# fat41p.net
KiCad netlist of a schematic drawn in Altium Designer
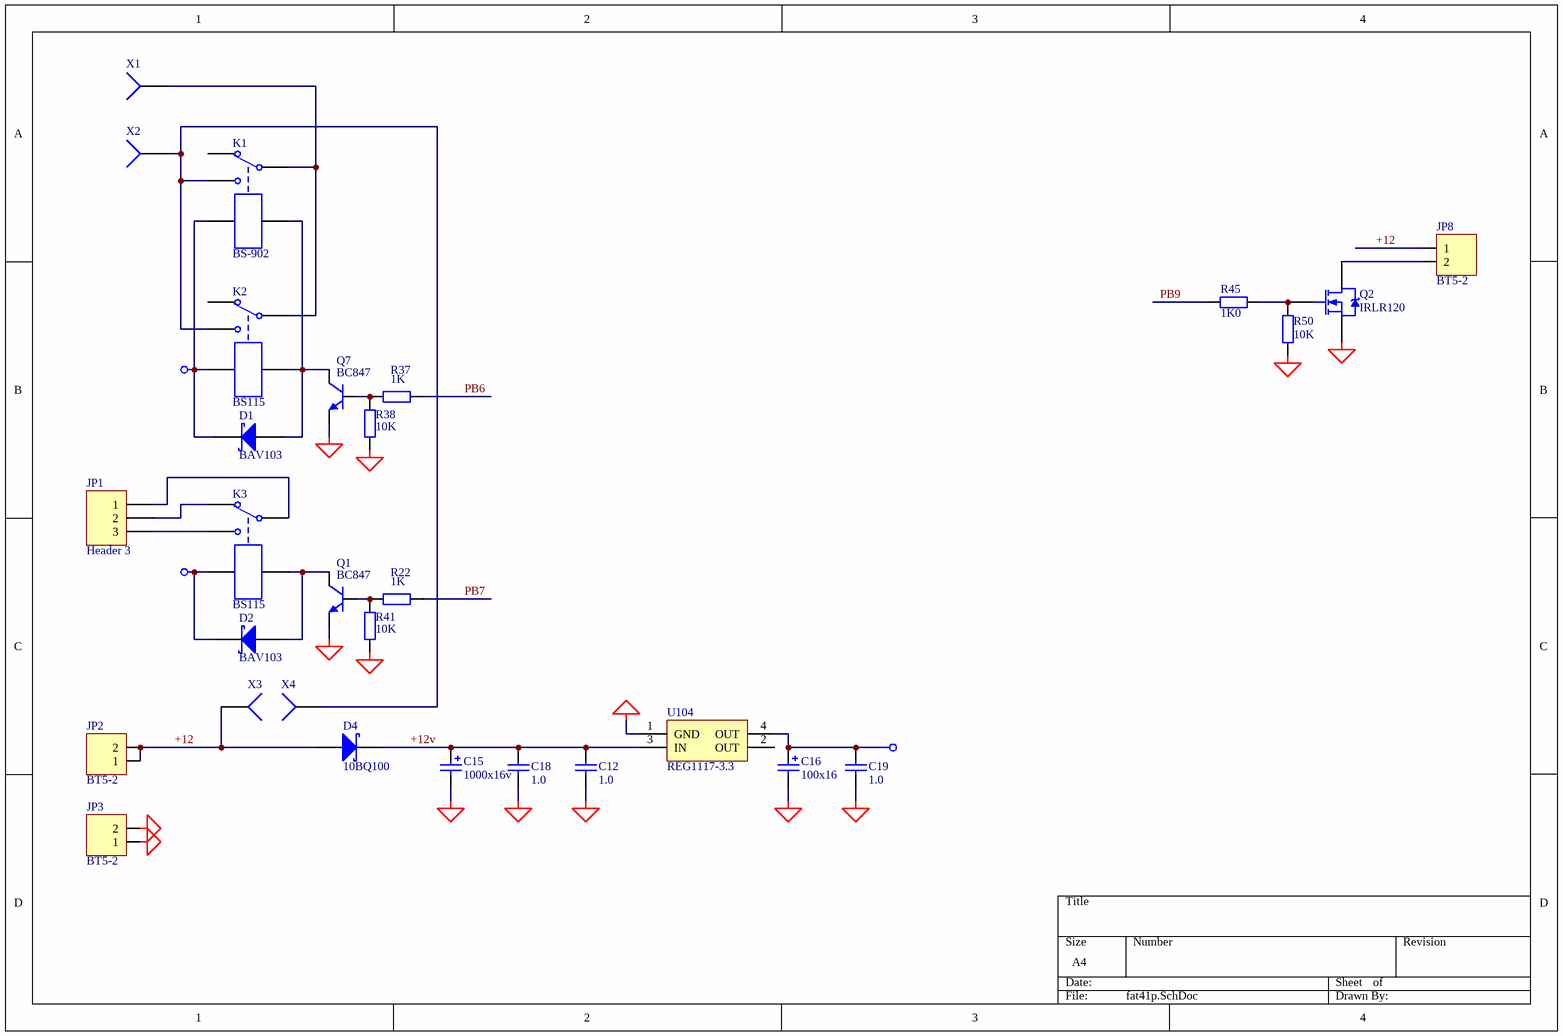
[diagram p0: fat41p.SchDoc]

(export (version "E")
  (design (tool "Eeschema 10.0.6"))
  (components
    (comp (ref "C12")
      (value "Cap")
      (footprint "_1206")
      (description "Capacitor")
      (fields
        (field (name "MANUFACTURER") "Generic Components")
        (field (name "ALTIUM_VALUE") "1.0")
        (field (name "PUBLISHER") "Altium Limited")
      )
      (libsource (lib "BUF") (part "Cap"))
    )
    (comp (ref "C15")
      (value "1000x16v")
      (footprint "el5")
      (description "Polarized Capacitor (Radial)")
      (fields (field (name "MANUFACTURER") "Generic Components") (field (name "PUBLISHER") "Altium Limited"))
      (libsource (lib "BUF") (part "Cap Pol1"))
    )
    (comp (ref "C16")
      (value "100x16")
      (footprint "el3")
      (description "Polarized Capacitor (Radial)")
      (fields (field (name "MANUFACTURER") "Generic Components") (field (name "PUBLISHER") "Altium Limited"))
      (libsource (lib "BUF") (part "Cap Pol"))
    )
    (comp (ref "C18")
      (value "Cap")
      (footprint "_1206")
      (description "Capacitor")
      (fields
        (field (name "MANUFACTURER") "Generic Components")
        (field (name "ALTIUM_VALUE") "1.0")
        (field (name "PUBLISHER") "Altium Limited")
      )
      (libsource (lib "BUF") (part "Cap"))
    )
    (comp (ref "C19")
      (value "Cap")
      (footprint "_1206")
      (description "Capacitor")
      (fields
        (field (name "MANUFACTURER") "Generic Components")
        (field (name "ALTIUM_VALUE") "1.0")
        (field (name "PUBLISHER") "Altium Limited")
      )
      (libsource (lib "BUF") (part "Cap"))
    )
    (comp (ref "D1")
      (value "BAV103")
      (footprint "_1206d")
      (description "Schottky Rectifier")
      (fields
        (field (name "MANUFACTURER") "International Rectifier")
        (field (name "PUBLISHER") "Altium Limited")
      )
      (libsource (lib "IR Discrete Diode") (part "10BQ015"))
    )
    (comp (ref "D2")
      (value "BAV103")
      (footprint "_1206d")
      (description "Schottky Rectifier")
      (fields
        (field (name "MANUFACTURER") "International Rectifier")
        (field (name "PUBLISHER") "Altium Limited")
      )
      (libsource (lib "IR Discrete Diode") (part "10BQ015"))
    )
    (comp (ref "D4")
      (value "10BQ100")
      (footprint "DSO-C2/X2.3")
      (description "Schottky Rectifier")
      (fields
        (field (name "MANUFACTURER") "International Rectifier")
        (field (name "PUBLISHER") "Altium Limited")
      )
      (libsource (lib "IR Discrete Diode") (part "10BQ015"))
    )
    (comp (ref "JP1")
      (value "Header 3")
      (footprint "BT5-3")
      (description "Header, 3-Pin")
      (fields (field (name "MANUFACTURER") "Generic Components") (field (name "PUBLISHER") "Altium Limited"))
      (libsource (lib "Miscellaneous Connectors") (part "Header 3"))
    )
    (comp (ref "JP2")
      (value "BT5-2")
      (footprint "BT5-2-1")
      (description "Header, 3-Pin")
      (fields (field (name "MANUFACTURER") "Generic Components") (field (name "PUBLISHER") "Altium Limited"))
      (libsource (lib "") (part "BT5-2_1"))
    )
    (comp (ref "JP3")
      (value "BT5-2")
      (footprint "BT5-2-1")
      (description "Header, 3-Pin")
      (fields (field (name "MANUFACTURER") "Generic Components") (field (name "PUBLISHER") "Altium Limited"))
      (libsource (lib "") (part "BT5-2_1"))
    )
    (comp (ref "JP8")
      (value "BT5-2")
      (footprint "BT5-2-1")
      (description "Header, 3-Pin")
      (fields (field (name "MANUFACTURER") "Generic Components") (field (name "PUBLISHER") "Altium Limited"))
      (libsource (lib "PAL") (part "BT5-2"))
    )
    (comp (ref "K1")
      (value "BS-902")
      (footprint "BS-902")
      (description "Single-Pole Dual-Throw Relay")
      (fields (field (name "MANUFACTURER") "Generic Components") (field (name "PUBLISHER") "Altium Limited"))
      (libsource (lib "PAL") (part "BS115"))
    )
    (comp (ref "K2")
      (value "BS115")
      (footprint "BS115")
      (description "Single-Pole Dual-Throw Relay")
      (fields (field (name "MANUFACTURER") "Generic Components") (field (name "PUBLISHER") "Altium Limited"))
      (libsource (lib "PAL") (part "BS115"))
    )
    (comp (ref "K3")
      (value "BS115")
      (footprint "BS115")
      (description "Single-Pole Dual-Throw Relay")
      (fields (field (name "MANUFACTURER") "Generic Components") (field (name "PUBLISHER") "Altium Limited"))
      (libsource (lib "PAL") (part "BS115"))
    )
    (comp (ref "Q1")
      (value "BC847")
      (footprint "SO-G3")
      (description "General Purpose Transistor NPN Silicon")
      (fields (field (name "MANUFACTURER") "Motorola") (field (name "PUBLISHER") "Altium Limited"))
      (libsource (lib "PAL") (part "BC847ALT1"))
    )
    (comp (ref "Q2")
      (value "IRLR120")
      (footprint "SIP-G3/E8")
      (description "HEXFET N-Channel Power MOSFET")
      (fields
        (field (name "MANUFACTURER") "International Rectifier")
        (field (name "PUBLISHER") "Altium Limited")
      )
      (libsource (lib "IR Discrete MOSFET") (part "IRFR120"))
    )
    (comp (ref "Q7")
      (value "BC847")
      (footprint "SO-G3")
      (description "General Purpose Transistor NPN Silicon")
      (fields (field (name "MANUFACTURER") "Motorola") (field (name "PUBLISHER") "Altium Limited"))
      (libsource (lib "PAL") (part "BC847ALT1"))
    )
    (comp (ref "R22")
      (value "Res2")
      (footprint "_1206")
      (description "Resistor")
      (fields
        (field (name "MANUFACTURER") "Generic Components")
        (field (name "ALTIUM_VALUE") "1K")
        (field (name "PUBLISHER") "Altium Limited")
      )
      (libsource (lib "Miscellaneous Devices") (part "Res2"))
    )
    (comp (ref "R37")
      (value "Res2")
      (footprint "_1206")
      (description "Resistor")
      (fields
        (field (name "MANUFACTURER") "Generic Components")
        (field (name "ALTIUM_VALUE") "1K")
        (field (name "PUBLISHER") "Altium Limited")
      )
      (libsource (lib "Miscellaneous Devices") (part "Res2"))
    )
    (comp (ref "R38")
      (value "Res2")
      (footprint "_1206")
      (description "Resistor")
      (fields
        (field (name "MANUFACTURER") "Generic Components")
        (field (name "ALTIUM_VALUE") "10K")
        (field (name "PUBLISHER") "Altium Limited")
      )
      (libsource (lib "") (part "Res2_1"))
    )
    (comp (ref "R41")
      (value "Res2")
      (footprint "_1206")
      (description "Resistor")
      (fields
        (field (name "MANUFACTURER") "Generic Components")
        (field (name "ALTIUM_VALUE") "10K")
        (field (name "PUBLISHER") "Altium Limited")
      )
      (libsource (lib "") (part "Res2_1"))
    )
    (comp (ref "R45")
      (value "1K0")
      (footprint "_1206")
      (description "Resistor")
      (fields (field (name "MANUFACTURER") "Generic Components") (field (name "PUBLISHER") "Altium Limited"))
      (libsource (lib "Miscellaneous Devices") (part "Res2"))
    )
    (comp (ref "R50")
      (value "10K")
      (footprint "_1206")
      (description "Resistor")
      (fields (field (name "MANUFACTURER") "Generic Components") (field (name "PUBLISHER") "Altium Limited"))
      (libsource (lib "") (part "Res2_1"))
    )
    (comp (ref "U104")
      (value "REG1117-3.3")
      (footprint "SIP-G3/C7.4")
      (description "800mA and 1A Low Dropout Positive Regulator 2.85V, 3.3V, 5V, and Adjustable")
      (fields (field (name "MANUFACTURER") "Burr-Brown") (field (name "PUBLISHER") "Altium Limited"))
      (libsource (lib "BB Power Mgt Voltage Regulator") (part "REG1117-3.3"))
    )
    (comp (ref "X1")
      (value "~")
      (footprint "PAL:PIN3")
      (description "Socket")
      (fields (field (name "MANUFACTURER") "Generic Components") (field (name "PUBLISHER") "Altium Limited"))
      (libsource (lib "Miscellaneous Connectors") (part "Socket"))
    )
    (comp (ref "X2")
      (value "~")
      (footprint "PAL:PIN3")
      (description "Socket")
      (fields (field (name "MANUFACTURER") "Generic Components") (field (name "PUBLISHER") "Altium Limited"))
      (libsource (lib "Miscellaneous Connectors") (part "Socket"))
    )
    (comp (ref "X3")
      (value "~")
      (footprint "PIN1")
      (description "Socket")
      (fields (field (name "MANUFACTURER") "Generic Components") (field (name "PUBLISHER") "Altium Limited"))
      (libsource (lib "Miscellaneous Connectors") (part "Socket"))
    )
    (comp (ref "X4")
      (value "~")
      (footprint "PIN1")
      (description "Socket")
      (fields (field (name "MANUFACTURER") "Generic Components") (field (name "PUBLISHER") "Altium Limited"))
      (libsource (lib "Miscellaneous Connectors") (part "Socket"))
    )
  )
  (nets
    (net (code "1") (name "+3v3") (class "Default")
      (node (ref "C16") (pin "1") (pinfunction "1_1") (pintype "passive"))
      (node (ref "C19") (pin "2") (pinfunction "2_2") (pintype "passive"))
      (node (ref "U104") (pin "4") (pinfunction "OUT_4") (pintype "power_in"))
    )
    (net (code "2") (name "+12v") (class "Default")
      (node (ref "C12") (pin "2") (pinfunction "2_2") (pintype "passive"))
      (node (ref "C15") (pin "1") (pinfunction "1_1") (pintype "passive"))
      (node (ref "C18") (pin "2") (pinfunction "2_2") (pintype "passive"))
      (node (ref "D1") (pin "2") (pinfunction "K_2") (pintype "passive"))
      (node (ref "D2") (pin "2") (pinfunction "K_2") (pintype "passive"))
      (node (ref "D4") (pin "2") (pinfunction "K_2") (pintype "passive"))
      (node (ref "K1") (pin "5") (pinfunction "5_5") (pintype "passive"))
      (node (ref "K2") (pin "5") (pinfunction "5_5") (pintype "passive"))
      (node (ref "K3") (pin "5") (pinfunction "5_5") (pintype "passive"))
      (node (ref "U104") (pin "3") (pinfunction "IN_3") (pintype "power_in"))
    )
    (net (code "3") (name "/+12") (class "Default")
      (node (ref "D4") (pin "1") (pinfunction "A_1") (pintype "passive"))
      (node (ref "JP2") (pin "1") (pinfunction "1_1") (pintype "passive"))
      (node (ref "JP2") (pin "2") (pinfunction "2_2") (pintype "passive"))
      (node (ref "JP8") (pin "1") (pinfunction "1_1") (pintype "passive"))
      (node (ref "X3") (pin "1") (pinfunction "1_1") (pintype "passive"))
    )
    (net (code "4") (name "/PB6") (class "Default")
      (node (ref "R37") (pin "2") (pinfunction "2_2") (pintype "passive"))
    )
    (net (code "5") (name "/PB7") (class "Default")
      (node (ref "R22") (pin "2") (pinfunction "2_2") (pintype "passive"))
    )
    (net (code "6") (name "/PB9") (class "Default")
      (node (ref "R45") (pin "1") (pinfunction "1_1") (pintype "passive"))
    )
    (net (code "7") (name "GND") (class "Default")
      (node (ref "C12") (pin "1") (pinfunction "1_1") (pintype "passive"))
      (node (ref "C15") (pin "2") (pinfunction "2_2") (pintype "passive"))
      (node (ref "C16") (pin "2") (pinfunction "2_2") (pintype "passive"))
      (node (ref "C18") (pin "1") (pinfunction "1_1") (pintype "passive"))
      (node (ref "C19") (pin "1") (pinfunction "1_1") (pintype "passive"))
      (node (ref "JP3") (pin "1") (pinfunction "1_1") (pintype "passive"))
      (node (ref "JP3") (pin "2") (pinfunction "2_2") (pintype "passive"))
      (node (ref "Q1") (pin "2") (pinfunction "E_2") (pintype "passive"))
      (node (ref "Q2") (pin "3") (pinfunction "S_3") (pintype "passive"))
      (node (ref "Q7") (pin "2") (pinfunction "E_2") (pintype "passive"))
      (node (ref "R38") (pin "2") (pinfunction "2_2") (pintype "passive"))
      (node (ref "R41") (pin "2") (pinfunction "2_2") (pintype "passive"))
      (node (ref "R50") (pin "2") (pinfunction "2_2") (pintype "passive"))
      (node (ref "U104") (pin "1") (pinfunction "GND_1") (pintype "power_in"))
    )
    (net (code "8") (name "Net-(D1-A)") (class "Default")
      (node (ref "D1") (pin "1") (pinfunction "A_1") (pintype "passive"))
      (node (ref "K1") (pin "4") (pinfunction "4_4") (pintype "passive"))
      (node (ref "K2") (pin "4") (pinfunction "4_4") (pintype "passive"))
      (node (ref "Q7") (pin "3") (pinfunction "C_3") (pintype "passive"))
    )
    (net (code "9") (name "Net-(D2-A)") (class "Default")
      (node (ref "D2") (pin "1") (pinfunction "A_1") (pintype "passive"))
      (node (ref "K3") (pin "4") (pinfunction "4_4") (pintype "passive"))
      (node (ref "Q1") (pin "3") (pinfunction "C_3") (pintype "passive"))
    )
    (net (code "10") (name "Net-(JP1-Pad1)") (class "Default")
      (node (ref "JP1") (pin "1") (pinfunction "1_1") (pintype "passive"))
      (node (ref "K3") (pin "1") (pinfunction "1_1") (pintype "passive"))
    )
    (net (code "11") (name "Net-(JP1-Pad2)") (class "Default")
      (node (ref "JP1") (pin "2") (pinfunction "2_2") (pintype "passive"))
      (node (ref "K3") (pin "2") (pinfunction "2_2") (pintype "passive"))
    )
    (net (code "12") (name "Net-(JP1-Pad3)") (class "Default")
      (node (ref "JP1") (pin "3") (pinfunction "3_3") (pintype "passive"))
      (node (ref "K3") (pin "3") (pinfunction "3_3") (pintype "passive"))
    )
    (net (code "13") (name "Net-(K1-Pad1)") (class "Default")
      (node (ref "K1") (pin "1") (pinfunction "1_1") (pintype "passive"))
      (node (ref "K2") (pin "1") (pinfunction "1_1") (pintype "passive"))
      (node (ref "X1") (pin "1") (pinfunction "1_1") (pintype "passive"))
    )
    (net (code "14") (name "Net-(K1-Pad3)") (class "Default")
      (node (ref "K1") (pin "3") (pinfunction "3_3") (pintype "passive"))
      (node (ref "K2") (pin "3") (pinfunction "3_3") (pintype "passive"))
      (node (ref "X2") (pin "1") (pinfunction "1_1") (pintype "passive"))
      (node (ref "X4") (pin "1") (pinfunction "1_1") (pintype "passive"))
    )
    (net (code "15") (name "Net-(Q1-B)") (class "Default")
      (node (ref "Q1") (pin "1") (pinfunction "B_1") (pintype "passive"))
      (node (ref "R22") (pin "1") (pinfunction "1_1") (pintype "passive"))
      (node (ref "R41") (pin "1") (pinfunction "1_1") (pintype "passive"))
    )
    (net (code "16") (name "Net-(Q2-D)") (class "Default")
      (node (ref "JP8") (pin "2") (pinfunction "2_2") (pintype "passive"))
      (node (ref "Q2") (pin "4") (pinfunction "D_4") (pintype "passive"))
    )
    (net (code "17") (name "Net-(Q2-G)") (class "Default")
      (node (ref "Q2") (pin "1") (pinfunction "G_1") (pintype "passive"))
      (node (ref "R45") (pin "2") (pinfunction "2_2") (pintype "passive"))
      (node (ref "R50") (pin "1") (pinfunction "1_1") (pintype "passive"))
    )
    (net (code "18") (name "Net-(Q7-B)") (class "Default")
      (node (ref "Q7") (pin "1") (pinfunction "B_1") (pintype "passive"))
      (node (ref "R37") (pin "1") (pinfunction "1_1") (pintype "passive"))
      (node (ref "R38") (pin "1") (pinfunction "1_1") (pintype "passive"))
    )
    (net (code "19") (name "unconnected-(K1-Pad2)") (class "Default")
      (node (ref "K1") (pin "2") (pinfunction "2_2") (pintype "passive"))
    )
    (net (code "20") (name "unconnected-(K2-Pad2)") (class "Default")
      (node (ref "K2") (pin "2") (pinfunction "2_2") (pintype "passive"))
    )
    (net (code "21") (name "unconnected-(U104-OUT-Pad2)") (class "Default")
      (node (ref "U104") (pin "2") (pinfunction "OUT_2") (pintype "power_in"))
    )
  )
)
